# Xedk.net
KiCad netlist of a schematic drawn in Altium Designer
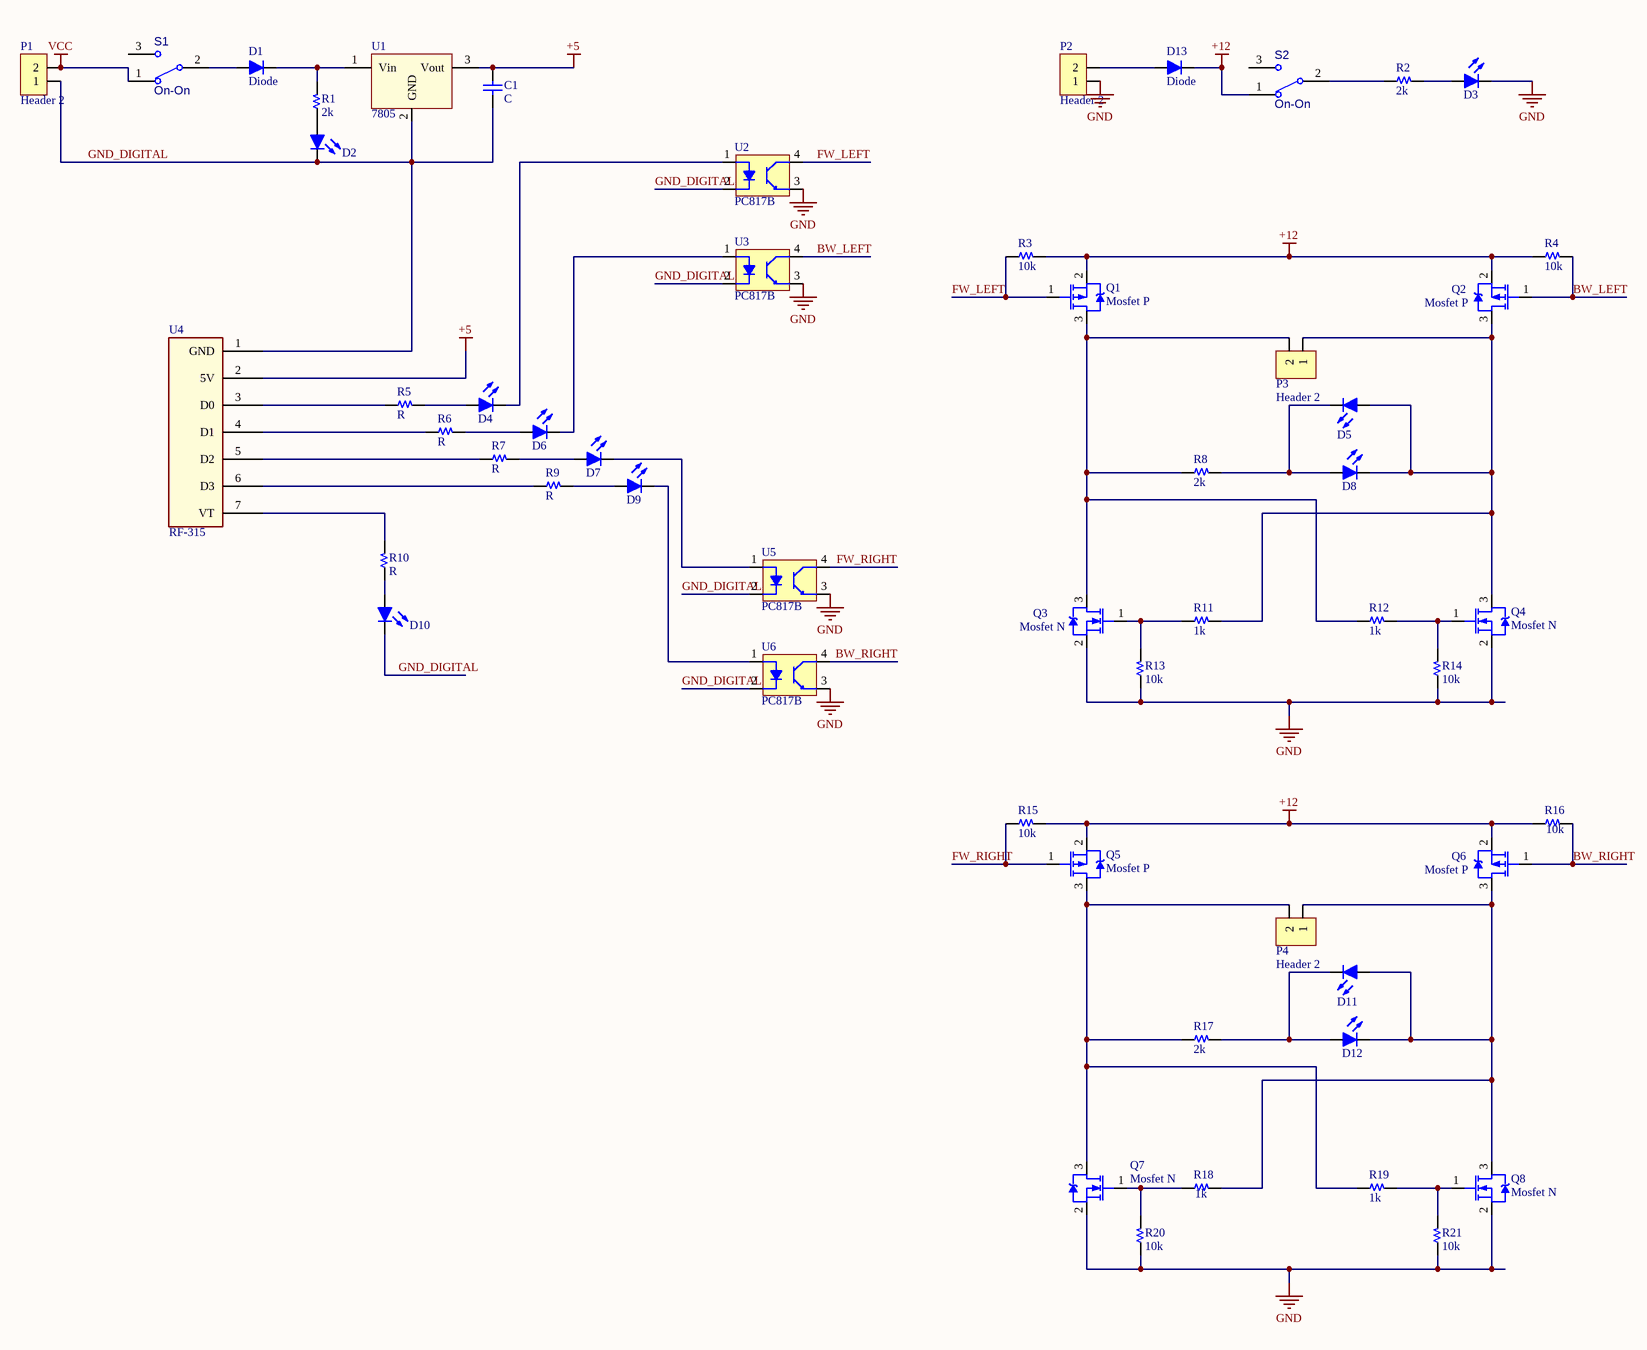
[diagram p0: Xedk.SchDoc]

(export (version "E")
  (design (tool "Eeschema 10.0.6"))
  (components
    (comp (ref "C1")
      (value "C")
      (footprint "CAP Ceramic/W300")
      (description "Capacitor non-pol")
      (libsource (lib "Xedieukhien") (part "Capacitor NP"))
    )
    (comp (ref "D1")
      (value "Diode")
      (footprint "DO-41")
      (description "Default Diode")
      (libsource (lib "Xedieukhien") (part "Diode"))
    )
    (comp (ref "D2")
      (value "Led")
      (footprint "LED 5MM - GREEN")
      (description "Typical LED")
      (libsource (lib "Xedieukhien") (part "Led"))
    )
    (comp (ref "D3")
      (value "Led")
      (footprint "LED 5MM - GREEN")
      (description "Typical LED")
      (libsource (lib "Xedieukhien") (part "Led"))
    )
    (comp (ref "D4")
      (value "Led")
      (footprint "LED 5MM - RED")
      (description "Typical LED")
      (libsource (lib "Xedieukhien") (part "Led"))
    )
    (comp (ref "D5")
      (value "Led")
      (footprint "LED 5MM - RED")
      (description "Typical LED")
      (libsource (lib "Xedieukhien") (part "Led"))
    )
    (comp (ref "D6")
      (value "Led")
      (footprint "LED 5MM - RED")
      (description "Typical LED")
      (libsource (lib "Xedieukhien") (part "Led"))
    )
    (comp (ref "D7")
      (value "Led")
      (footprint "LED 5MM - RED")
      (description "Typical LED")
      (libsource (lib "Xedieukhien") (part "Led"))
    )
    (comp (ref "D8")
      (value "Led")
      (footprint "LED 5MM - GREEN")
      (description "Typical LED")
      (libsource (lib "Xedieukhien") (part "Led"))
    )
    (comp (ref "D9")
      (value "Led")
      (footprint "LED 5MM - RED")
      (description "Typical LED")
      (libsource (lib "Xedieukhien") (part "Led"))
    )
    (comp (ref "D10")
      (value "Led")
      (footprint "LED 5MM - RED")
      (description "Typical LED")
      (libsource (lib "Xedieukhien") (part "Led"))
    )
    (comp (ref "D11")
      (value "Led")
      (footprint "LED 5MM - RED")
      (description "Typical LED")
      (libsource (lib "Xedieukhien") (part "Led"))
    )
    (comp (ref "D12")
      (value "Led")
      (footprint "LED 5MM - GREEN")
      (description "Typical LED")
      (libsource (lib "Xedieukhien") (part "Led"))
    )
    (comp (ref "D13")
      (value "Diode")
      (footprint "DO-41")
      (description "Default Diode")
      (libsource (lib "Xedieukhien") (part "Diode"))
    )
    (comp (ref "P1")
      (value "Header 2")
      (footprint "HDR/Terminal/2/5mm")
      (description "Header, 2-Pin")
      (libsource (lib "") (part "Header 2_1"))
    )
    (comp (ref "P2")
      (value "Header 2")
      (footprint "HDR/Terminal/2/5mm")
      (description "Header, 2-Pin")
      (libsource (lib "") (part "Header 2_1"))
    )
    (comp (ref "P3")
      (value "Header 2")
      (footprint "HDR/Terminal/2/5mm")
      (description "Header, 2-Pin")
      (libsource (lib "Xedieukhien") (part "Header 2"))
    )
    (comp (ref "P4")
      (value "Header 2")
      (footprint "HDR/Terminal/2/5mm")
      (description "Header, 2-Pin")
      (libsource (lib "Xedieukhien") (part "Header 2"))
    )
    (comp (ref "Q1")
      (value "Mosfet P")
      (footprint "TO-220")
      (libsource (lib "Xedieukhien") (part "Mosfet P"))
    )
    (comp (ref "Q2")
      (value "Mosfet P")
      (footprint "TO-220")
      (libsource (lib "Xedieukhien") (part "Mosfet P"))
    )
    (comp (ref "Q3")
      (value "Mosfet N")
      (footprint "TO-220")
      (libsource (lib "Xedieukhien") (part "Mosfet N"))
    )
    (comp (ref "Q4")
      (value "Mosfet N")
      (footprint "TO-220")
      (libsource (lib "Xedieukhien") (part "Mosfet N"))
    )
    (comp (ref "Q5")
      (value "Mosfet P")
      (footprint "TO-220")
      (libsource (lib "Xedieukhien") (part "Mosfet P"))
    )
    (comp (ref "Q6")
      (value "Mosfet P")
      (footprint "TO-220")
      (libsource (lib "Xedieukhien") (part "Mosfet P"))
    )
    (comp (ref "Q7")
      (value "Mosfet N")
      (footprint "TO-220")
      (libsource (lib "Xedieukhien") (part "Mosfet N"))
    )
    (comp (ref "Q8")
      (value "Mosfet N")
      (footprint "TO-220")
      (libsource (lib "Xedieukhien") (part "Mosfet N"))
    )
    (comp (ref "R1")
      (value "2k")
      (footprint "R 1/4W/300")
      (description "Resistor")
      (libsource (lib "Xedieukhien") (part "Resistor"))
    )
    (comp (ref "R2")
      (value "2k")
      (footprint "R 1/4W/300")
      (description "Resistor")
      (libsource (lib "Xedieukhien") (part "Resistor"))
    )
    (comp (ref "R3")
      (value "10k")
      (footprint "R 1/4W/300")
      (description "Resistor")
      (libsource (lib "Xedieukhien") (part "Resistor"))
    )
    (comp (ref "R4")
      (value "10k")
      (footprint "R 1/4W/300")
      (description "Resistor")
      (libsource (lib "Xedieukhien") (part "Resistor"))
    )
    (comp (ref "R5")
      (value "R")
      (footprint "R 1/4W/300")
      (description "Resistor")
      (libsource (lib "Xedieukhien") (part "Resistor"))
    )
    (comp (ref "R6")
      (value "R")
      (footprint "R 1/4W/300")
      (description "Resistor")
      (libsource (lib "Xedieukhien") (part "Resistor"))
    )
    (comp (ref "R7")
      (value "R")
      (footprint "R 1/4W/300")
      (description "Resistor")
      (libsource (lib "Xedieukhien") (part "Resistor"))
    )
    (comp (ref "R8")
      (value "2k")
      (footprint "R 1/4W/300")
      (description "Resistor")
      (libsource (lib "Xedieukhien") (part "Resistor"))
    )
    (comp (ref "R9")
      (value "R")
      (footprint "R 1/4W/300")
      (description "Resistor")
      (libsource (lib "Xedieukhien") (part "Resistor"))
    )
    (comp (ref "R10")
      (value "R")
      (footprint "R 1/4W/300")
      (description "Resistor")
      (libsource (lib "Xedieukhien") (part "Resistor"))
    )
    (comp (ref "R11")
      (value "1k")
      (footprint "R 1/4W/300")
      (description "Resistor")
      (libsource (lib "Xedieukhien") (part "Resistor"))
    )
    (comp (ref "R12")
      (value "1k")
      (footprint "R 1/4W/300")
      (description "Resistor")
      (libsource (lib "Xedieukhien") (part "Resistor"))
    )
    (comp (ref "R13")
      (value "10k")
      (footprint "R 1/4W/300")
      (description "Resistor")
      (libsource (lib "Xedieukhien") (part "Resistor"))
    )
    (comp (ref "R14")
      (value "10k")
      (footprint "R 1/4W/300")
      (description "Resistor")
      (libsource (lib "Xedieukhien") (part "Resistor"))
    )
    (comp (ref "R15")
      (value "10k")
      (footprint "R 1/4W/300")
      (description "Resistor")
      (libsource (lib "Xedieukhien") (part "Resistor"))
    )
    (comp (ref "R16")
      (value "10k")
      (footprint "R 1/4W/300")
      (description "Resistor")
      (libsource (lib "Xedieukhien") (part "Resistor"))
    )
    (comp (ref "R17")
      (value "2k")
      (footprint "R 1/4W/300")
      (description "Resistor")
      (libsource (lib "Xedieukhien") (part "Resistor"))
    )
    (comp (ref "R18")
      (value "1k")
      (footprint "R 1/4W/300")
      (description "Resistor")
      (libsource (lib "Xedieukhien") (part "Resistor"))
    )
    (comp (ref "R19")
      (value "1k")
      (footprint "R 1/4W/300")
      (description "Resistor")
      (libsource (lib "Xedieukhien") (part "Resistor"))
    )
    (comp (ref "R20")
      (value "10k")
      (footprint "R 1/4W/300")
      (description "Resistor")
      (libsource (lib "Xedieukhien") (part "Resistor"))
    )
    (comp (ref "R21")
      (value "10k")
      (footprint "R 1/4W/300")
      (description "Resistor")
      (libsource (lib "Xedieukhien") (part "Resistor"))
    )
    (comp (ref "S1")
      (value "ON-ON")
      (footprint "SWITCH_SPDT_SLIDER")
      (description "Switch THD vertical toggle SPDT")
      (fields (field (name "SWITCH FUNCTION") "On-On"))
      (libsource (lib "Xedieukhien") (part "SW_THD_SPDT_On-On"))
    )
    (comp (ref "S2")
      (value "ON-ON")
      (footprint "SWITCH_SPDT_SLIDER")
      (description "Switch THD vertical toggle SPDT")
      (fields (field (name "SWITCH FUNCTION") "On-On"))
      (libsource (lib "Xedieukhien") (part "SW_THD_SPDT_On-On"))
    )
    (comp (ref "U1")
      (value "7805")
      (footprint "TO-220")
      (description "LDO Fixed Voltage regulator")
      (libsource (lib "Xedieukhien") (part "78xx"))
    )
    (comp (ref "U2")
      (value "PC817B")
      (footprint "DIP 4")
      (libsource (lib "Xedieukhien") (part "Opto PC817B"))
    )
    (comp (ref "U3")
      (value "PC817B")
      (footprint "DIP 4")
      (libsource (lib "Xedieukhien") (part "Opto PC817B"))
    )
    (comp (ref "U4")
      (value "RF-315")
      (footprint "RF-315 7 pins")
      (libsource (lib "Xedieukhien") (part "RF-315"))
    )
    (comp (ref "U5")
      (value "PC817B")
      (footprint "DIP 4")
      (libsource (lib "Xedieukhien") (part "Opto PC817B"))
    )
    (comp (ref "U6")
      (value "PC817B")
      (footprint "DIP 4")
      (libsource (lib "Xedieukhien") (part "Opto PC817B"))
    )
  )
  (nets
    (net (code "1") (name "+5") (class "Default")
      (node (ref "C1") (pin "1") (pinfunction "1_1") (pintype "passive"))
      (node (ref "U1") (pin "3") (pinfunction "Vout_3") (pintype "passive"))
      (node (ref "U4") (pin "2") (pinfunction "5V_2") (pintype "passive"))
    )
    (net (code "2") (name "+12") (class "Default")
      (node (ref "D13") (pin "2") (pinfunction "K_2") (pintype "passive"))
      (node (ref "Q1") (pin "2") (pinfunction "S_2") (pintype "passive"))
      (node (ref "Q2") (pin "2") (pinfunction "S_2") (pintype "passive"))
      (node (ref "Q5") (pin "2") (pinfunction "S_2") (pintype "passive"))
      (node (ref "Q6") (pin "2") (pinfunction "S_2") (pintype "passive"))
      (node (ref "R15") (pin "2") (pinfunction "2_2") (pintype "passive"))
      (node (ref "R16") (pin "1") (pinfunction "1_1") (pintype "passive"))
      (node (ref "R3") (pin "2") (pinfunction "2_2") (pintype "passive"))
      (node (ref "R4") (pin "1") (pinfunction "1_1") (pintype "passive"))
      (node (ref "S2") (pin "1") (pinfunction "1_1") (pintype "passive"))
    )
    (net (code "3") (name "/BW_LEFT") (class "Default")
      (node (ref "Q2") (pin "1") (pinfunction "G_1") (pintype "passive"))
      (node (ref "R4") (pin "2") (pinfunction "2_2") (pintype "passive"))
      (node (ref "U3") (pin "4") (pinfunction "C_4") (pintype "passive"))
    )
    (net (code "4") (name "/BW_RIGHT") (class "Default")
      (node (ref "Q6") (pin "1") (pinfunction "G_1") (pintype "passive"))
      (node (ref "R16") (pin "2") (pinfunction "2_2") (pintype "passive"))
      (node (ref "U6") (pin "4") (pinfunction "C_4") (pintype "passive"))
    )
    (net (code "5") (name "/FW_LEFT") (class "Default")
      (node (ref "Q1") (pin "1") (pinfunction "G_1") (pintype "passive"))
      (node (ref "R3") (pin "1") (pinfunction "1_1") (pintype "passive"))
      (node (ref "U2") (pin "4") (pinfunction "C_4") (pintype "passive"))
    )
    (net (code "6") (name "/FW_RIGHT") (class "Default")
      (node (ref "Q5") (pin "1") (pinfunction "G_1") (pintype "passive"))
      (node (ref "R15") (pin "1") (pinfunction "1_1") (pintype "passive"))
      (node (ref "U5") (pin "4") (pinfunction "C_4") (pintype "passive"))
    )
    (net (code "7") (name "/GND_DIGITAL") (class "Default")
      (node (ref "C1") (pin "2") (pinfunction "2_2") (pintype "passive"))
      (node (ref "D10") (pin "2") (pinfunction "K_2") (pintype "passive"))
      (node (ref "D2") (pin "2") (pinfunction "K_2") (pintype "passive"))
      (node (ref "P1") (pin "1") (pinfunction "1_1") (pintype "passive"))
      (node (ref "U1") (pin "2") (pinfunction "GND_2") (pintype "passive"))
      (node (ref "U2") (pin "2") (pinfunction "K_2") (pintype "passive"))
      (node (ref "U3") (pin "2") (pinfunction "K_2") (pintype "passive"))
      (node (ref "U4") (pin "1") (pinfunction "GND_1") (pintype "passive"))
      (node (ref "U5") (pin "2") (pinfunction "K_2") (pintype "passive"))
      (node (ref "U6") (pin "2") (pinfunction "K_2") (pintype "passive"))
    )
    (net (code "8") (name "GND") (class "Default")
      (node (ref "D3") (pin "2") (pinfunction "K_2") (pintype "passive"))
      (node (ref "P2") (pin "1") (pinfunction "1_1") (pintype "passive"))
      (node (ref "Q3") (pin "2") (pinfunction "S_2") (pintype "passive"))
      (node (ref "Q4") (pin "2") (pinfunction "S_2") (pintype "passive"))
      (node (ref "Q7") (pin "2") (pinfunction "S_2") (pintype "passive"))
      (node (ref "Q8") (pin "2") (pinfunction "S_2") (pintype "passive"))
      (node (ref "R13") (pin "1") (pinfunction "1_1") (pintype "passive"))
      (node (ref "R14") (pin "1") (pinfunction "1_1") (pintype "passive"))
      (node (ref "R20") (pin "1") (pinfunction "1_1") (pintype "passive"))
      (node (ref "R21") (pin "1") (pinfunction "1_1") (pintype "passive"))
      (node (ref "U2") (pin "3") (pinfunction "E_3") (pintype "passive"))
      (node (ref "U3") (pin "3") (pinfunction "E_3") (pintype "passive"))
      (node (ref "U5") (pin "3") (pinfunction "E_3") (pintype "passive"))
      (node (ref "U6") (pin "3") (pinfunction "E_3") (pintype "passive"))
    )
    (net (code "9") (name "Net-(D1-A)") (class "Default")
      (node (ref "D1") (pin "1") (pinfunction "A_1") (pintype "passive"))
      (node (ref "S1") (pin "2") (pinfunction "2_2") (pintype "passive"))
    )
    (net (code "10") (name "Net-(D1-K)") (class "Default")
      (node (ref "D1") (pin "2") (pinfunction "K_2") (pintype "passive"))
      (node (ref "R1") (pin "2") (pinfunction "2_2") (pintype "passive"))
      (node (ref "U1") (pin "1") (pinfunction "Vin_1") (pintype "power_in"))
    )
    (net (code "11") (name "Net-(D2-A)") (class "Default")
      (node (ref "D2") (pin "1") (pinfunction "A_1") (pintype "passive"))
      (node (ref "R1") (pin "1") (pinfunction "1_1") (pintype "passive"))
    )
    (net (code "12") (name "Net-(D3-A)") (class "Default")
      (node (ref "D3") (pin "1") (pinfunction "A_1") (pintype "passive"))
      (node (ref "R2") (pin "2") (pinfunction "2_2") (pintype "passive"))
    )
    (net (code "13") (name "Net-(D4-A)") (class "Default")
      (node (ref "D4") (pin "1") (pinfunction "A_1") (pintype "passive"))
      (node (ref "R5") (pin "2") (pinfunction "2_2") (pintype "passive"))
    )
    (net (code "14") (name "Net-(D4-K)") (class "Default")
      (node (ref "D4") (pin "2") (pinfunction "K_2") (pintype "passive"))
      (node (ref "U2") (pin "1") (pinfunction "A_1") (pintype "passive"))
    )
    (net (code "15") (name "Net-(D5-A)") (class "Default")
      (node (ref "D5") (pin "1") (pinfunction "A_1") (pintype "passive"))
      (node (ref "D8") (pin "2") (pinfunction "K_2") (pintype "passive"))
      (node (ref "P3") (pin "1") (pinfunction "1_1") (pintype "passive"))
      (node (ref "Q2") (pin "3") (pinfunction "D_3") (pintype "passive"))
      (node (ref "Q4") (pin "3") (pinfunction "D_3") (pintype "passive"))
      (node (ref "R11") (pin "2") (pinfunction "2_2") (pintype "passive"))
    )
    (net (code "16") (name "Net-(D5-K)") (class "Default")
      (node (ref "D5") (pin "2") (pinfunction "K_2") (pintype "passive"))
      (node (ref "D8") (pin "1") (pinfunction "A_1") (pintype "passive"))
      (node (ref "R8") (pin "2") (pinfunction "2_2") (pintype "passive"))
    )
    (net (code "17") (name "Net-(D6-A)") (class "Default")
      (node (ref "D6") (pin "1") (pinfunction "A_1") (pintype "passive"))
      (node (ref "R6") (pin "2") (pinfunction "2_2") (pintype "passive"))
    )
    (net (code "18") (name "Net-(D6-K)") (class "Default")
      (node (ref "D6") (pin "2") (pinfunction "K_2") (pintype "passive"))
      (node (ref "U3") (pin "1") (pinfunction "A_1") (pintype "passive"))
    )
    (net (code "19") (name "Net-(D7-A)") (class "Default")
      (node (ref "D7") (pin "1") (pinfunction "A_1") (pintype "passive"))
      (node (ref "R7") (pin "2") (pinfunction "2_2") (pintype "passive"))
    )
    (net (code "20") (name "Net-(D7-K)") (class "Default")
      (node (ref "D7") (pin "2") (pinfunction "K_2") (pintype "passive"))
      (node (ref "U5") (pin "1") (pinfunction "A_1") (pintype "passive"))
    )
    (net (code "21") (name "Net-(D9-A)") (class "Default")
      (node (ref "D9") (pin "1") (pinfunction "A_1") (pintype "passive"))
      (node (ref "R9") (pin "2") (pinfunction "2_2") (pintype "passive"))
    )
    (net (code "22") (name "Net-(D9-K)") (class "Default")
      (node (ref "D9") (pin "2") (pinfunction "K_2") (pintype "passive"))
      (node (ref "U6") (pin "1") (pinfunction "A_1") (pintype "passive"))
    )
    (net (code "23") (name "Net-(D10-A)") (class "Default")
      (node (ref "D10") (pin "1") (pinfunction "A_1") (pintype "passive"))
      (node (ref "R10") (pin "1") (pinfunction "1_1") (pintype "passive"))
    )
    (net (code "24") (name "Net-(D11-A)") (class "Default")
      (node (ref "D11") (pin "1") (pinfunction "A_1") (pintype "passive"))
      (node (ref "D12") (pin "2") (pinfunction "K_2") (pintype "passive"))
      (node (ref "P4") (pin "1") (pinfunction "1_1") (pintype "passive"))
      (node (ref "Q6") (pin "3") (pinfunction "D_3") (pintype "passive"))
      (node (ref "Q8") (pin "3") (pinfunction "D_3") (pintype "passive"))
      (node (ref "R18") (pin "2") (pinfunction "2_2") (pintype "passive"))
    )
    (net (code "25") (name "Net-(D11-K)") (class "Default")
      (node (ref "D11") (pin "2") (pinfunction "K_2") (pintype "passive"))
      (node (ref "D12") (pin "1") (pinfunction "A_1") (pintype "passive"))
      (node (ref "R17") (pin "2") (pinfunction "2_2") (pintype "passive"))
    )
    (net (code "26") (name "Net-(D13-A)") (class "Default")
      (node (ref "D13") (pin "1") (pinfunction "A_1") (pintype "passive"))
      (node (ref "P2") (pin "2") (pinfunction "2_2") (pintype "passive"))
    )
    (net (code "27") (name "Net-(Q1-D)") (class "Default")
      (node (ref "P3") (pin "2") (pinfunction "2_2") (pintype "passive"))
      (node (ref "Q1") (pin "3") (pinfunction "D_3") (pintype "passive"))
      (node (ref "Q3") (pin "3") (pinfunction "D_3") (pintype "passive"))
      (node (ref "R12") (pin "1") (pinfunction "1_1") (pintype "passive"))
      (node (ref "R8") (pin "1") (pinfunction "1_1") (pintype "passive"))
    )
    (net (code "28") (name "Net-(Q3-G)") (class "Default")
      (node (ref "Q3") (pin "1") (pinfunction "G_1") (pintype "passive"))
      (node (ref "R11") (pin "1") (pinfunction "1_1") (pintype "passive"))
      (node (ref "R13") (pin "2") (pinfunction "2_2") (pintype "passive"))
    )
    (net (code "29") (name "Net-(Q4-G)") (class "Default")
      (node (ref "Q4") (pin "1") (pinfunction "G_1") (pintype "passive"))
      (node (ref "R12") (pin "2") (pinfunction "2_2") (pintype "passive"))
      (node (ref "R14") (pin "2") (pinfunction "2_2") (pintype "passive"))
    )
    (net (code "30") (name "Net-(Q5-D)") (class "Default")
      (node (ref "P4") (pin "2") (pinfunction "2_2") (pintype "passive"))
      (node (ref "Q5") (pin "3") (pinfunction "D_3") (pintype "passive"))
      (node (ref "Q7") (pin "3") (pinfunction "D_3") (pintype "passive"))
      (node (ref "R17") (pin "1") (pinfunction "1_1") (pintype "passive"))
      (node (ref "R19") (pin "1") (pinfunction "1_1") (pintype "passive"))
    )
    (net (code "31") (name "Net-(Q7-G)") (class "Default")
      (node (ref "Q7") (pin "1") (pinfunction "G_1") (pintype "passive"))
      (node (ref "R18") (pin "1") (pinfunction "1_1") (pintype "passive"))
      (node (ref "R20") (pin "2") (pinfunction "2_2") (pintype "passive"))
    )
    (net (code "32") (name "Net-(Q8-G)") (class "Default")
      (node (ref "Q8") (pin "1") (pinfunction "G_1") (pintype "passive"))
      (node (ref "R19") (pin "2") (pinfunction "2_2") (pintype "passive"))
      (node (ref "R21") (pin "2") (pinfunction "2_2") (pintype "passive"))
    )
    (net (code "33") (name "Net-(R2-Pad1)") (class "Default")
      (node (ref "R2") (pin "1") (pinfunction "1_1") (pintype "passive"))
      (node (ref "S2") (pin "2") (pinfunction "2_2") (pintype "passive"))
    )
    (net (code "34") (name "Net-(U4-D0)") (class "Default")
      (node (ref "R5") (pin "1") (pinfunction "1_1") (pintype "passive"))
      (node (ref "U4") (pin "3") (pinfunction "D0_3") (pintype "passive"))
    )
    (net (code "35") (name "Net-(U4-D1)") (class "Default")
      (node (ref "R6") (pin "1") (pinfunction "1_1") (pintype "passive"))
      (node (ref "U4") (pin "4") (pinfunction "D1_4") (pintype "passive"))
    )
    (net (code "36") (name "Net-(U4-D2)") (class "Default")
      (node (ref "R7") (pin "1") (pinfunction "1_1") (pintype "passive"))
      (node (ref "U4") (pin "5") (pinfunction "D2_5") (pintype "passive"))
    )
    (net (code "37") (name "Net-(U4-D3)") (class "Default")
      (node (ref "R9") (pin "1") (pinfunction "1_1") (pintype "passive"))
      (node (ref "U4") (pin "6") (pinfunction "D3_6") (pintype "passive"))
    )
    (net (code "38") (name "Net-(U4-VT)") (class "Default")
      (node (ref "R10") (pin "2") (pinfunction "2_2") (pintype "passive"))
      (node (ref "U4") (pin "7") (pinfunction "VT_7") (pintype "passive"))
    )
    (net (code "39") (name "VCC") (class "Default")
      (node (ref "P1") (pin "2") (pinfunction "2_2") (pintype "passive"))
      (node (ref "S1") (pin "1") (pinfunction "1_1") (pintype "passive"))
    )
    (net (code "40") (name "unconnected-(S1-Pad3)") (class "Default")
      (node (ref "S1") (pin "3") (pinfunction "3_3") (pintype "passive"))
    )
    (net (code "41") (name "unconnected-(S2-Pad3)") (class "Default")
      (node (ref "S2") (pin "3") (pinfunction "3_3") (pintype "passive"))
    )
  )
)
